# MPU6050-IMU_I2C_V1.net
KiCad netlist of a schematic drawn in EAGLE
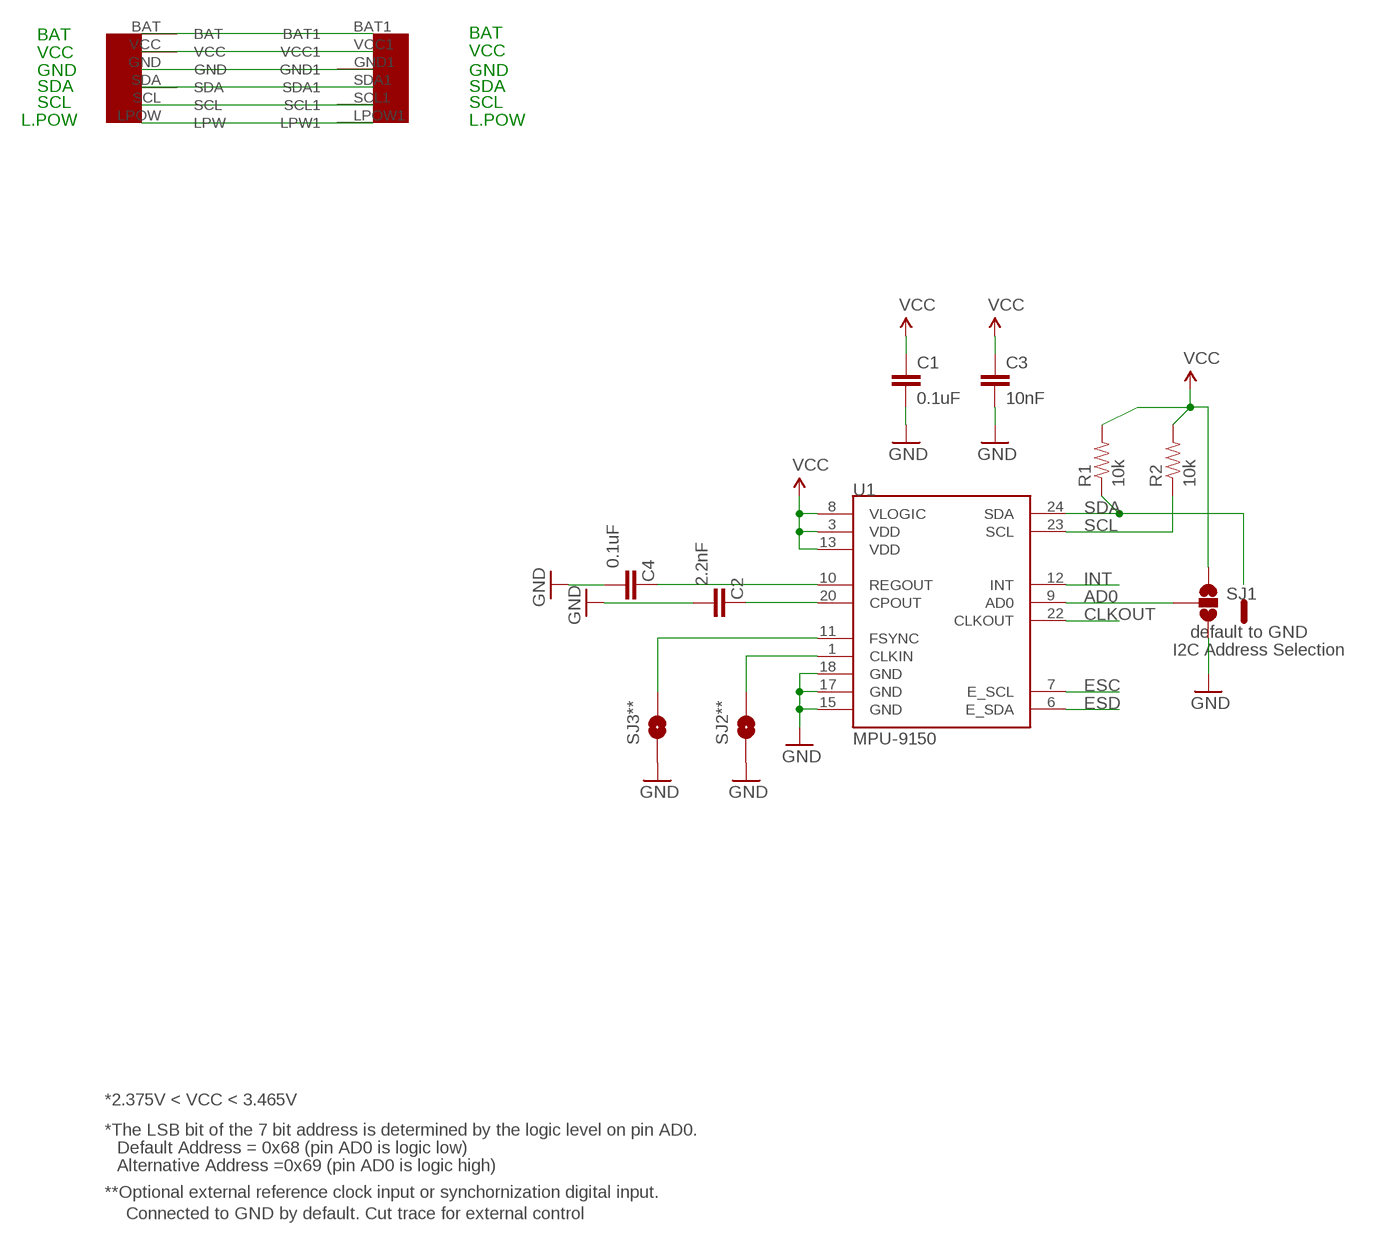
[diagram p0: schematic, sheet 1]

(export (version "E")
  (design (tool "Eeschema 10.0.6"))
  (components
    (comp (ref "C1")
      (value "0.1uF")
      (footprint "eagle-import:0402-CAP")
      (fields (field (name "MF") "AVX") (field (name "MPN") "02016D104KAT2A"))
      (libsource (lib "eagle-import") (part "CAP0402-CAP"))
    )
    (comp (ref "C2")
      (value "2.2nF")
      (footprint "eagle-import:0402-CAP")
      (fields (field (name "MF") "AVX") (field (name "MPN") "06035C222KAT2A"))
      (libsource (lib "eagle-import") (part "CAP0402-CAP"))
    )
    (comp (ref "C3")
      (value "10nF")
      (footprint "eagle-import:0402-CAP")
      (fields (field (name "MF") "AVX") (field (name "MPN") "06035G103ZAT2A"))
      (libsource (lib "eagle-import") (part "CAP0402-CAP"))
    )
    (comp (ref "C4")
      (value "0.1uF")
      (footprint "eagle-import:0402-CAP")
      (fields (field (name "MF") "AVX") (field (name "MPN") "02016D104KAT2A"))
      (libsource (lib "eagle-import") (part "CAP0402-CAP"))
    )
    (comp (ref "R1")
      (value "10k")
      (footprint "eagle-import:0402-RES")
      (libsource (lib "eagle-import") (part "RESISTOR0402-RES"))
    )
    (comp (ref "R2")
      (value "10k")
      (footprint "eagle-import:0402-RES")
      (libsource (lib "eagle-import") (part "RESISTOR0402-RES"))
    )
    (comp (ref "SJ1")
      (value "SOLDERJUMPER_2WAYPASTE2&3")
      (footprint "eagle-import:SJ_3_PASTE2&3")
      (libsource (lib "eagle-import") (part "SOLDERJUMPER_2WAYPASTE2&3"))
    )
    (comp (ref "SJ2**")
      (value "SOLDERJUMPERTRACE")
      (footprint "eagle-import:SJ_2S-TRACE")
      (libsource (lib "eagle-import") (part "SOLDERJUMPERTRACE"))
    )
    (comp (ref "SJ3**")
      (value "SOLDERJUMPERTRACE")
      (footprint "eagle-import:SJ_2S-TRACE")
      (libsource (lib "eagle-import") (part "SOLDERJUMPERTRACE"))
    )
    (comp (ref "U$1")
      (value "EASYI2C6PINHEADER")
      (footprint "eagle-import:EASYI2C6PINHEADER")
      (libsource (lib "eagle-import") (part "EASYI2C6PINHEADER"))
    )
    (comp (ref "U1")
      (value "MPU-9150")
      (footprint "eagle-import:QFN-24-NP")
      (libsource (lib "eagle-import") (part "MPU-9150QFN-24-NP"))
    )
  )
  (nets
    (net (code "1") (name "/AD0") (class "Default")
      (node (ref "SJ1") (pin "2") (pinfunction "2_2") (pintype "passive"))
      (node (ref "U1") (pin "9") (pinfunction "AD0_9") (pintype "bidirectional"))
    )
    (net (code "2") (name "/CLKOUT") (class "Default")
      (node (ref "U1") (pin "22") (pinfunction "CLKOUT_22") (pintype "bidirectional"))
    )
    (net (code "3") (name "/ESC") (class "Default")
      (node (ref "U1") (pin "7") (pinfunction "E_SCL_7") (pintype "bidirectional"))
    )
    (net (code "4") (name "/ESD") (class "Default")
      (node (ref "U1") (pin "6") (pinfunction "E_SDA_6") (pintype "bidirectional"))
    )
    (net (code "5") (name "/INT") (class "Default")
      (node (ref "U1") (pin "12") (pinfunction "INT_12") (pintype "bidirectional"))
    )
    (net (code "6") (name "/SCL") (class "Default")
      (node (ref "R2") (pin "1") (pinfunction "1_1") (pintype "passive"))
      (node (ref "U$1") (pin "SCL") (pinfunction "SCL_SCL") (pintype "bidirectional"))
      (node (ref "U$1") (pin "SCL1") (pinfunction "SCL1_SCL1") (pintype "bidirectional"))
      (node (ref "U1") (pin "23") (pinfunction "SCL_23") (pintype "bidirectional"))
    )
    (net (code "7") (name "/SDA") (class "Default")
      (node (ref "R1") (pin "1") (pinfunction "1_1") (pintype "passive"))
      (node (ref "U$1") (pin "SDA") (pinfunction "SDA_SDA") (pintype "bidirectional"))
      (node (ref "U$1") (pin "SDA1") (pinfunction "SDA1_SDA1") (pintype "bidirectional"))
      (node (ref "U1") (pin "24") (pinfunction "SDA_24") (pintype "bidirectional"))
    )
    (net (code "8") (name "GND") (class "Default")
      (node (ref "C1") (pin "2") (pinfunction "2_2") (pintype "passive"))
      (node (ref "C2") (pin "2") (pinfunction "2_2") (pintype "passive"))
      (node (ref "C3") (pin "2") (pinfunction "2_2") (pintype "passive"))
      (node (ref "C4") (pin "2") (pinfunction "2_2") (pintype "passive"))
      (node (ref "SJ1") (pin "3") (pinfunction "3_3") (pintype "passive"))
      (node (ref "SJ2**") (pin "1") (pinfunction "1_1") (pintype "passive"))
      (node (ref "SJ3**") (pin "1") (pinfunction "1_1") (pintype "passive"))
      (node (ref "U$1") (pin "GND") (pinfunction "GND_GND") (pintype "bidirectional"))
      (node (ref "U$1") (pin "GND1") (pinfunction "GND1_GND1") (pintype "bidirectional"))
      (node (ref "U1") (pin "15") (pinfunction "GND_15") (pintype "bidirectional"))
      (node (ref "U1") (pin "17") (pinfunction "GND_17") (pintype "bidirectional"))
      (node (ref "U1") (pin "18") (pinfunction "GND_18") (pintype "bidirectional"))
    )
    (net (code "9") (name "Net-(U$1-LPW)") (class "Default")
      (node (ref "U$1") (pin "LPOW") (pinfunction "LPW_LPOW") (pintype "bidirectional"))
      (node (ref "U$1") (pin "LPOW1") (pinfunction "LPW1_LPOW1") (pintype "bidirectional"))
    )
    (net (code "10") (name "Net-(U$1-PadBAT)") (class "Default")
      (node (ref "U$1") (pin "BAT") (pinfunction "BAT_BAT") (pintype "bidirectional"))
      (node (ref "U$1") (pin "BAT1") (pinfunction "BAT1_BAT1") (pintype "bidirectional"))
    )
    (net (code "11") (name "Net-(U1-CLKIN)") (class "Default")
      (node (ref "SJ2**") (pin "2") (pinfunction "2_2") (pintype "passive"))
      (node (ref "U1") (pin "1") (pinfunction "CLKIN_1") (pintype "bidirectional"))
    )
    (net (code "12") (name "Net-(U1-CPOUT)") (class "Default")
      (node (ref "C2") (pin "1") (pinfunction "1_1") (pintype "passive"))
      (node (ref "U1") (pin "20") (pinfunction "CPOUT_20") (pintype "bidirectional"))
    )
    (net (code "13") (name "Net-(U1-FSYNC)") (class "Default")
      (node (ref "SJ3**") (pin "2") (pinfunction "2_2") (pintype "passive"))
      (node (ref "U1") (pin "11") (pinfunction "FSYNC_11") (pintype "bidirectional"))
    )
    (net (code "14") (name "Net-(U1-REGOUT)") (class "Default")
      (node (ref "C4") (pin "1") (pinfunction "1_1") (pintype "passive"))
      (node (ref "U1") (pin "10") (pinfunction "REGOUT_10") (pintype "bidirectional"))
    )
    (net (code "15") (name "VCC") (class "Default")
      (node (ref "C1") (pin "1") (pinfunction "1_1") (pintype "passive"))
      (node (ref "C3") (pin "1") (pinfunction "1_1") (pintype "passive"))
      (node (ref "R1") (pin "2") (pinfunction "2_2") (pintype "passive"))
      (node (ref "R2") (pin "2") (pinfunction "2_2") (pintype "passive"))
      (node (ref "SJ1") (pin "1") (pinfunction "1_1") (pintype "passive"))
      (node (ref "U$1") (pin "VCC") (pinfunction "VCC_VCC") (pintype "bidirectional"))
      (node (ref "U$1") (pin "VCC1") (pinfunction "VCC1_VCC1") (pintype "bidirectional"))
      (node (ref "U1") (pin "13") (pinfunction "VDD_13") (pintype "bidirectional"))
      (node (ref "U1") (pin "3") (pinfunction "VDD_3") (pintype "bidirectional"))
      (node (ref "U1") (pin "8") (pinfunction "VLOGIC_8") (pintype "bidirectional"))
    )
  )
)
